# MEGAMOTHERBOARD.net
KiCad netlist of a schematic drawn in EAGLE
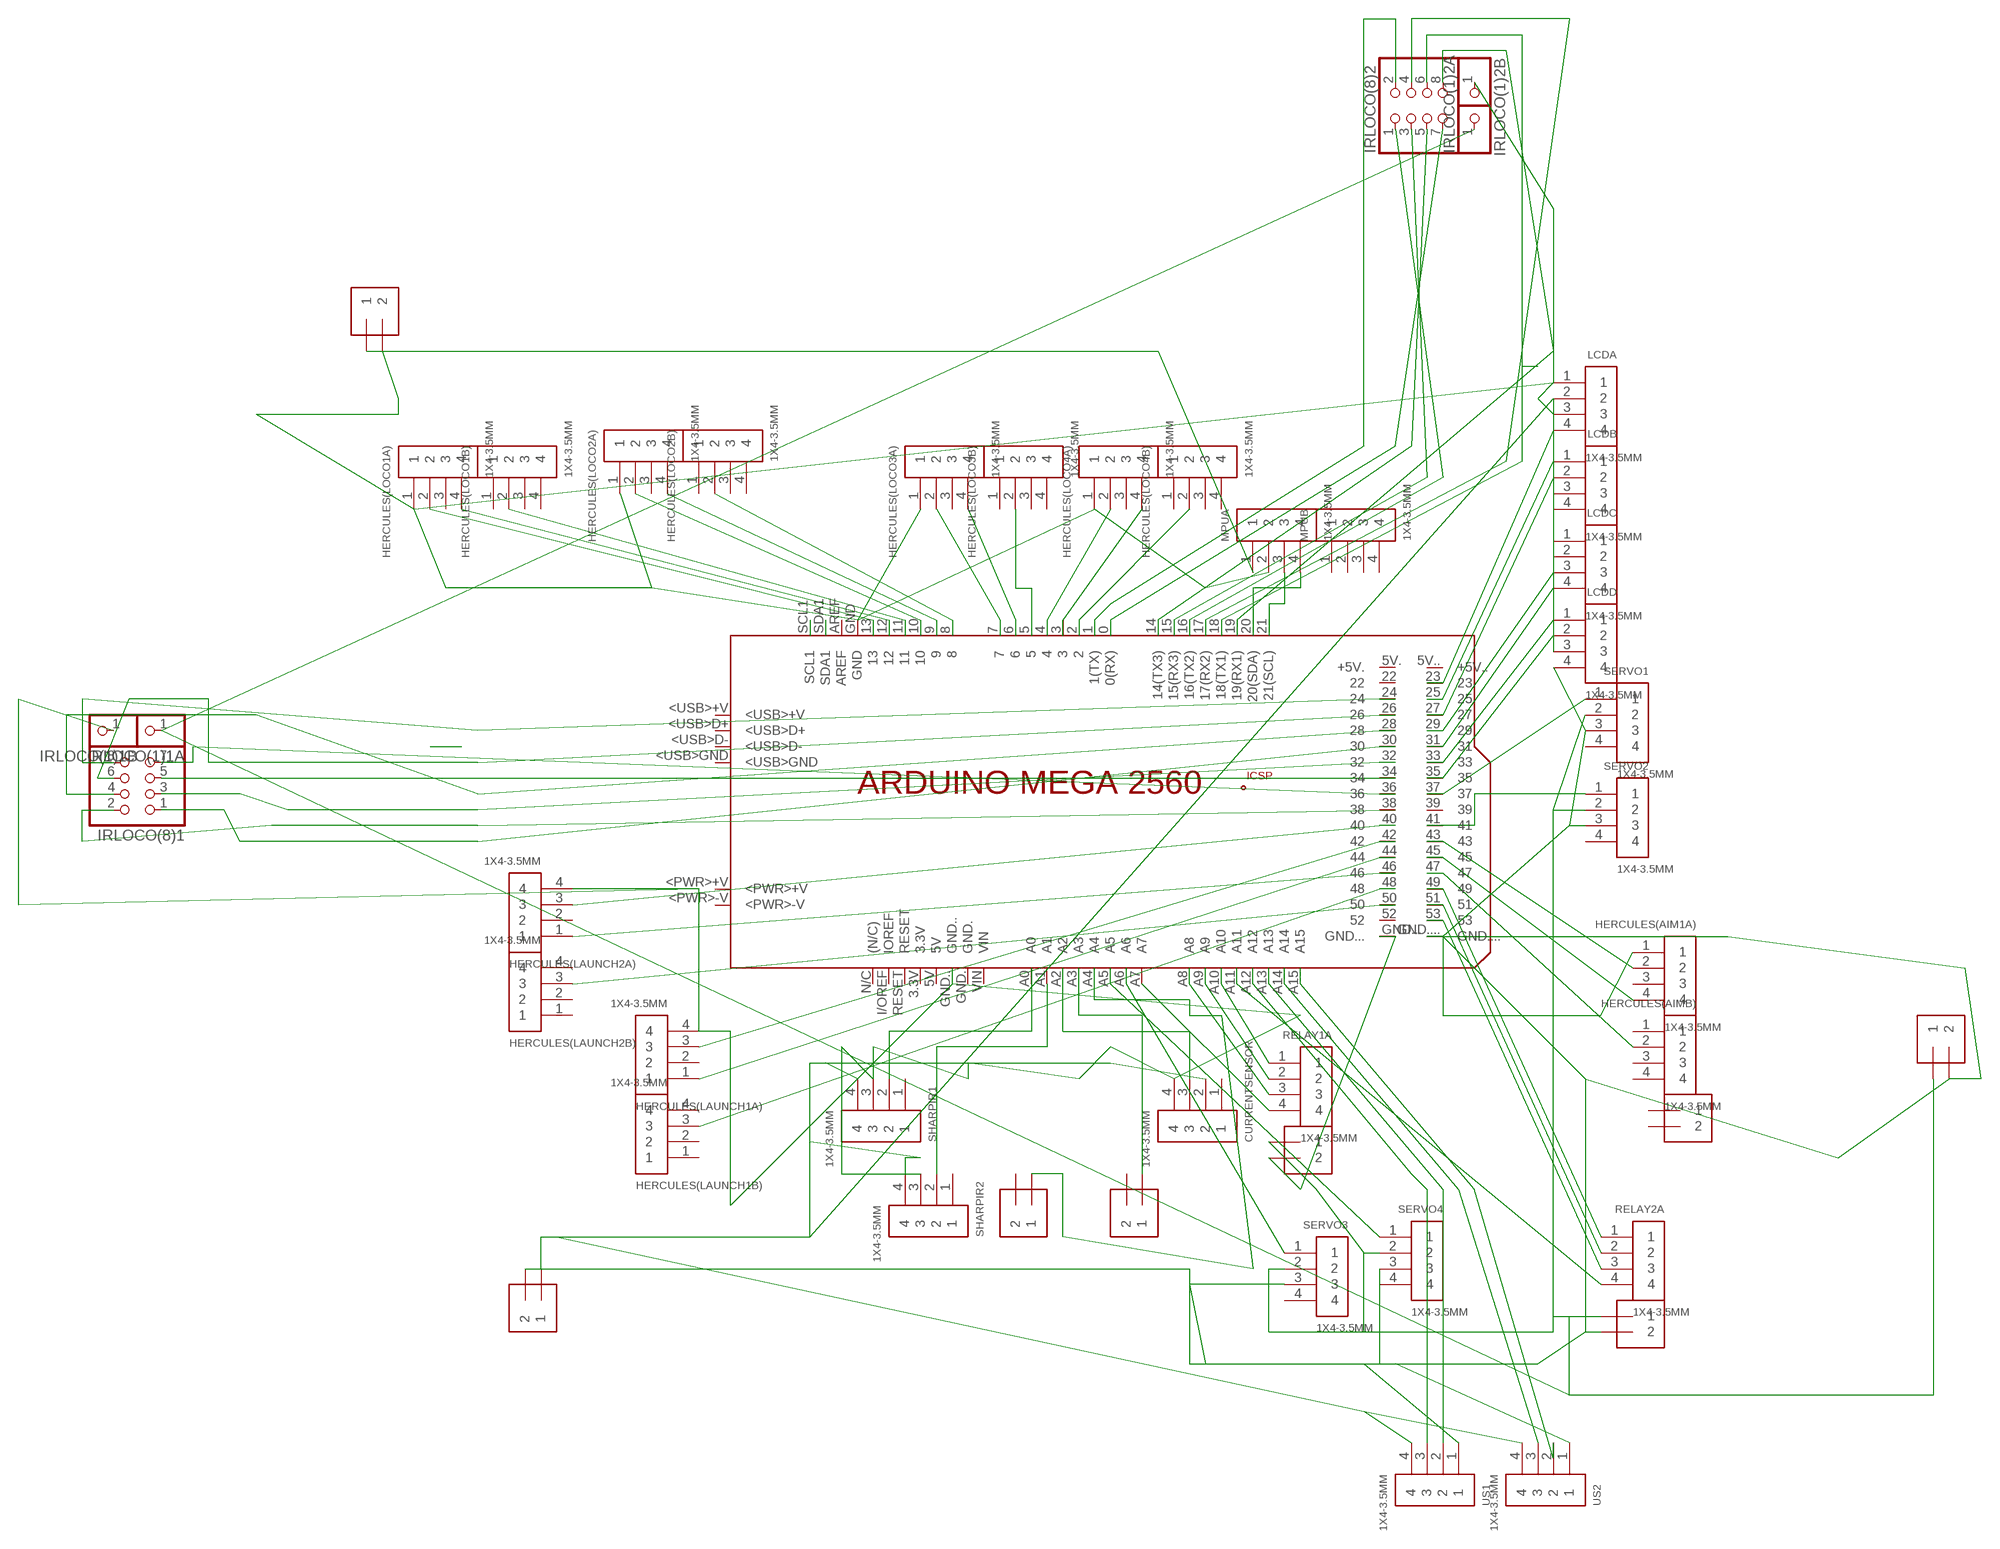
[diagram p0: schematic, sheet 1]

(export (version "E")
  (design (tool "Eeschema 10.0.6"))
  (components
    (comp (ref "3.3V")
      (value "1X2-3.5MM")
      (footprint "eagle-import:1X2-3.5MM")
      (libsource (lib "eagle-import") (part "1X2-3.5MM"))
    )
    (comp (ref "5V")
      (value "1X2-3.5MM")
      (footprint "eagle-import:1X2-3.5MM")
      (libsource (lib "eagle-import") (part "1X2-3.5MM"))
    )
    (comp (ref "12V")
      (value "1X2-3.5MM")
      (footprint "eagle-import:1X2-3.5MM")
      (libsource (lib "eagle-import") (part "1X2-3.5MM"))
    )
    (comp (ref "CURRENTSENSOR")
      (value "1X4-3.5MM")
      (footprint "eagle-import:1X04-3.5MM")
      (libsource (lib "eagle-import") (part "1X4-3.5MM"))
    )
    (comp (ref "HERCULES(AIM1A)")
      (value "1X4-3.5MM")
      (footprint "eagle-import:1X04-3.5MM")
      (libsource (lib "eagle-import") (part "1X4-3.5MM"))
    )
    (comp (ref "HERCULES(AIM1C)")
      (value "1X2-3.5MM")
      (footprint "eagle-import:1X2-3.5MM")
      (libsource (lib "eagle-import") (part "1X2-3.5MM"))
    )
    (comp (ref "HERCULES(AIMB)")
      (value "1X4-3.5MM")
      (footprint "eagle-import:1X04-3.5MM")
      (libsource (lib "eagle-import") (part "1X4-3.5MM"))
    )
    (comp (ref "HERCULES(LAUNCH1A)")
      (value "1X4-3.5MM")
      (footprint "eagle-import:1X04-3.5MM")
      (libsource (lib "eagle-import") (part "1X4-3.5MM"))
    )
    (comp (ref "HERCULES(LAUNCH1B)")
      (value "1X4-3.5MM")
      (footprint "eagle-import:1X04-3.5MM")
      (libsource (lib "eagle-import") (part "1X4-3.5MM"))
    )
    (comp (ref "HERCULES(LAUNCH2A)")
      (value "1X4-3.5MM")
      (footprint "eagle-import:1X04-3.5MM")
      (libsource (lib "eagle-import") (part "1X4-3.5MM"))
    )
    (comp (ref "HERCULES(LAUNCH2B)")
      (value "1X4-3.5MM")
      (footprint "eagle-import:1X04-3.5MM")
      (libsource (lib "eagle-import") (part "1X4-3.5MM"))
    )
    (comp (ref "HERCULES(LOCO1A)")
      (value "1X4-3.5MM")
      (footprint "eagle-import:1X04-3.5MM")
      (libsource (lib "eagle-import") (part "1X4-3.5MM"))
    )
    (comp (ref "HERCULES(LOCO1B)")
      (value "1X4-3.5MM")
      (footprint "eagle-import:1X04-3.5MM")
      (libsource (lib "eagle-import") (part "1X4-3.5MM"))
    )
    (comp (ref "HERCULES(LOCO2A)")
      (value "1X4-3.5MM")
      (footprint "eagle-import:1X04-3.5MM")
      (libsource (lib "eagle-import") (part "1X4-3.5MM"))
    )
    (comp (ref "HERCULES(LOCO2B)")
      (value "1X4-3.5MM")
      (footprint "eagle-import:1X04-3.5MM")
      (libsource (lib "eagle-import") (part "1X4-3.5MM"))
    )
    (comp (ref "HERCULES(LOCO3A)")
      (value "1X4-3.5MM")
      (footprint "eagle-import:1X04-3.5MM")
      (libsource (lib "eagle-import") (part "1X4-3.5MM"))
    )
    (comp (ref "HERCULES(LOCO3B)")
      (value "1X4-3.5MM")
      (footprint "eagle-import:1X04-3.5MM")
      (libsource (lib "eagle-import") (part "1X4-3.5MM"))
    )
    (comp (ref "HERCULES(LOCO4A)")
      (value "1X4-3.5MM")
      (footprint "eagle-import:1X04-3.5MM")
      (libsource (lib "eagle-import") (part "1X4-3.5MM"))
    )
    (comp (ref "HERCULES(LOCO4B)")
      (value "1X4-3.5MM")
      (footprint "eagle-import:1X04-3.5MM")
      (libsource (lib "eagle-import") (part "1X4-3.5MM"))
    )
    (comp (ref "IRLOCO(1)1A")
      (value "PINHD-1X1")
      (footprint "eagle-import:1X01")
      (libsource (lib "eagle-import") (part "PINHD-1X1"))
    )
    (comp (ref "IRLOCO(1)1B")
      (value "PINHD-1X1")
      (footprint "eagle-import:1X01")
      (libsource (lib "eagle-import") (part "PINHD-1X1"))
    )
    (comp (ref "IRLOCO(1)2A")
      (value "PINHD-1X1")
      (footprint "eagle-import:1X01")
      (libsource (lib "eagle-import") (part "PINHD-1X1"))
    )
    (comp (ref "IRLOCO(1)2B")
      (value "PINHD-1X1")
      (footprint "eagle-import:1X01")
      (libsource (lib "eagle-import") (part "PINHD-1X1"))
    )
    (comp (ref "IRLOCO(8)1")
      (value "PINHD-2X4")
      (footprint "eagle-import:2X04")
      (libsource (lib "eagle-import") (part "PINHD-2X4"))
    )
    (comp (ref "IRLOCO(8)2")
      (value "PINHD-2X4")
      (footprint "eagle-import:2X04")
      (libsource (lib "eagle-import") (part "PINHD-2X4"))
    )
    (comp (ref "IRLOCO1ANALOG")
      (value "1X2-3.5MM")
      (footprint "eagle-import:1X2-3.5MM")
      (libsource (lib "eagle-import") (part "1X2-3.5MM"))
    )
    (comp (ref "IRLOCO2ANALOG")
      (value "1X2-3.5MM")
      (footprint "eagle-import:1X2-3.5MM")
      (libsource (lib "eagle-import") (part "1X2-3.5MM"))
    )
    (comp (ref "LCDA")
      (value "1X4-3.5MM")
      (footprint "eagle-import:1X04-3.5MM")
      (libsource (lib "eagle-import") (part "1X4-3.5MM"))
    )
    (comp (ref "LCDB")
      (value "1X4-3.5MM")
      (footprint "eagle-import:1X04-3.5MM")
      (libsource (lib "eagle-import") (part "1X4-3.5MM"))
    )
    (comp (ref "LCDC")
      (value "1X4-3.5MM")
      (footprint "eagle-import:1X04-3.5MM")
      (libsource (lib "eagle-import") (part "1X4-3.5MM"))
    )
    (comp (ref "LCDD")
      (value "1X4-3.5MM")
      (footprint "eagle-import:1X04-3.5MM")
      (libsource (lib "eagle-import") (part "1X4-3.5MM"))
    )
    (comp (ref "MPUA")
      (value "1X4-3.5MM")
      (footprint "eagle-import:1X04-3.5MM")
      (libsource (lib "eagle-import") (part "1X4-3.5MM"))
    )
    (comp (ref "MPUB")
      (value "1X4-3.5MM")
      (footprint "eagle-import:1X04-3.5MM")
      (libsource (lib "eagle-import") (part "1X4-3.5MM"))
    )
    (comp (ref "PCB1")
      (value "ARDUINO_MEGA2560")
      (footprint "eagle-import:ARDUINO_MEGA2560")
      (libsource (lib "eagle-import") (part "ARDUINO_MEGA2560"))
    )
    (comp (ref "RELAY1A")
      (value "1X4-3.5MM")
      (footprint "eagle-import:1X04-3.5MM")
      (libsource (lib "eagle-import") (part "1X4-3.5MM"))
    )
    (comp (ref "RELAY1B")
      (value "1X2-3.5MM")
      (footprint "eagle-import:1X2-3.5MM")
      (libsource (lib "eagle-import") (part "1X2-3.5MM"))
    )
    (comp (ref "RELAY2A")
      (value "1X4-3.5MM")
      (footprint "eagle-import:1X04-3.5MM")
      (libsource (lib "eagle-import") (part "1X4-3.5MM"))
    )
    (comp (ref "RELAY2B")
      (value "1X2-3.5MM")
      (footprint "eagle-import:1X2-3.5MM")
      (libsource (lib "eagle-import") (part "1X2-3.5MM"))
    )
    (comp (ref "SERVO1")
      (value "1X4-3.5MM")
      (footprint "eagle-import:1X04-3.5MM")
      (libsource (lib "eagle-import") (part "1X4-3.5MM"))
    )
    (comp (ref "SERVO2")
      (value "1X4-3.5MM")
      (footprint "eagle-import:1X04-3.5MM")
      (libsource (lib "eagle-import") (part "1X4-3.5MM"))
    )
    (comp (ref "SERVO3")
      (value "1X4-3.5MM")
      (footprint "eagle-import:1X04-3.5MM")
      (libsource (lib "eagle-import") (part "1X4-3.5MM"))
    )
    (comp (ref "SERVO4")
      (value "1X4-3.5MM")
      (footprint "eagle-import:1X04-3.5MM")
      (libsource (lib "eagle-import") (part "1X4-3.5MM"))
    )
    (comp (ref "SHARPIR1")
      (value "1X4-3.5MM")
      (footprint "eagle-import:1X04-3.5MM")
      (libsource (lib "eagle-import") (part "1X4-3.5MM"))
    )
    (comp (ref "SHARPIR2")
      (value "1X4-3.5MM")
      (footprint "eagle-import:1X04-3.5MM")
      (libsource (lib "eagle-import") (part "1X4-3.5MM"))
    )
    (comp (ref "US1")
      (value "1X4-3.5MM")
      (footprint "eagle-import:1X04-3.5MM")
      (libsource (lib "eagle-import") (part "1X4-3.5MM"))
    )
    (comp (ref "US2")
      (value "1X4-3.5MM")
      (footprint "eagle-import:1X04-3.5MM")
      (libsource (lib "eagle-import") (part "1X4-3.5MM"))
    )
  )
  (nets
    (net (code "1") (name "Net-(3.3V-Pad1)") (class "Default")
      (node (ref "3.3V") (pin "1") (pinfunction "1_1") (pintype "passive"))
      (node (ref "MPUA") (pin "1") (pinfunction "1_1") (pintype "bidirectional"))
    )
    (net (code "2") (name "Net-(3.3V-Pad2)") (class "Default")
      (node (ref "3.3V") (pin "2") (pinfunction "2_2") (pintype "passive"))
      (node (ref "HERCULES(LOCO1A)") (pin "1") (pinfunction "1_1") (pintype "bidirectional"))
      (node (ref "HERCULES(LOCO2A)") (pin "1") (pinfunction "1_1") (pintype "bidirectional"))
      (node (ref "HERCULES(LOCO3A)") (pin "1") (pinfunction "1_1") (pintype "bidirectional"))
      (node (ref "HERCULES(LOCO4A)") (pin "1") (pinfunction "1_1") (pintype "bidirectional"))
      (node (ref "IRLOCO(1)2B") (pin "1") (pinfunction "1_1") (pintype "passive"))
      (node (ref "LCDA") (pin "1") (pinfunction "1_1") (pintype "bidirectional"))
      (node (ref "LCDA") (pin "3") (pinfunction "3_3") (pintype "bidirectional"))
      (node (ref "MPUA") (pin "2") (pinfunction "2_2") (pintype "bidirectional"))
      (node (ref "PCB1") (pin "GND") (pinfunction "GND_GND") (pintype "bidirectional"))
    )
    (net (code "3") (name "Net-(5V-Pad1)") (class "Default")
      (node (ref "5V") (pin "1") (pinfunction "1_1") (pintype "passive"))
      (node (ref "CURRENTSENSOR") (pin "2") (pinfunction "2_2") (pintype "bidirectional"))
      (node (ref "LCDA") (pin "2") (pinfunction "2_2") (pintype "bidirectional"))
      (node (ref "LCDD") (pin "3") (pinfunction "3_3") (pintype "bidirectional"))
      (node (ref "SHARPIR1") (pin "4") (pinfunction "4_4") (pintype "bidirectional"))
      (node (ref "SHARPIR2") (pin "4") (pinfunction "4_4") (pintype "bidirectional"))
      (node (ref "US1") (pin "4") (pinfunction "4_4") (pintype "bidirectional"))
      (node (ref "US2") (pin "4") (pinfunction "4_4") (pintype "bidirectional"))
    )
    (net (code "4") (name "Net-(12V-Pad1)") (class "Default")
      (node (ref "12V") (pin "1") (pinfunction "1_1") (pintype "passive"))
      (node (ref "IRLOCO(1)1A") (pin "1") (pinfunction "1_1") (pintype "passive"))
      (node (ref "IRLOCO(1)2A") (pin "1") (pinfunction "1_1") (pintype "passive"))
      (node (ref "RELAY1B") (pin "1") (pinfunction "1_1") (pintype "passive"))
      (node (ref "RELAY2B") (pin "1") (pinfunction "1_1") (pintype "passive"))
      (node (ref "SERVO1") (pin "2") (pinfunction "2_2") (pintype "bidirectional"))
      (node (ref "SERVO2") (pin "2") (pinfunction "2_2") (pintype "bidirectional"))
      (node (ref "SERVO3") (pin "2") (pinfunction "2_2") (pintype "bidirectional"))
      (node (ref "SERVO4") (pin "2") (pinfunction "2_2") (pintype "bidirectional"))
    )
    (net (code "5") (name "Net-(12V-Pad2)") (class "Default")
      (node (ref "12V") (pin "2") (pinfunction "2_2") (pintype "passive"))
      (node (ref "5V") (pin "2") (pinfunction "2_2") (pintype "passive"))
      (node (ref "HERCULES(AIM1A)") (pin "1") (pinfunction "1_1") (pintype "bidirectional"))
      (node (ref "LCDD") (pin "4") (pinfunction "4_4") (pintype "bidirectional"))
      (node (ref "PCB1") (pin "GND....") (pinfunction "GND...._GND....") (pintype "bidirectional"))
      (node (ref "RELAY2B") (pin "2") (pinfunction "2_2") (pintype "passive"))
      (node (ref "SERVO1") (pin "3") (pinfunction "3_3") (pintype "bidirectional"))
      (node (ref "SERVO2") (pin "3") (pinfunction "3_3") (pintype "bidirectional"))
      (node (ref "SERVO3") (pin "3") (pinfunction "3_3") (pintype "bidirectional"))
      (node (ref "SERVO4") (pin "3") (pinfunction "3_3") (pintype "bidirectional"))
      (node (ref "US1") (pin "1") (pinfunction "1_1") (pintype "bidirectional"))
      (node (ref "US2") (pin "1") (pinfunction "1_1") (pintype "bidirectional"))
    )
    (net (code "6") (name "Net-(CURRENTSENSOR-Pad3)") (class "Default")
      (node (ref "CURRENTSENSOR") (pin "3") (pinfunction "3_3") (pintype "bidirectional"))
      (node (ref "PCB1") (pin "A2") (pinfunction "A2_A2") (pintype "bidirectional"))
    )
    (net (code "7") (name "Net-(CURRENTSENSOR-Pad4)") (class "Default")
      (node (ref "CURRENTSENSOR") (pin "4") (pinfunction "4_4") (pintype "bidirectional"))
      (node (ref "HERCULES(LAUNCH1A)") (pin "4") (pinfunction "4_4") (pintype "bidirectional"))
      (node (ref "HERCULES(LAUNCH2A)") (pin "4") (pinfunction "4_4") (pintype "bidirectional"))
      (node (ref "IRLOCO(1)1B") (pin "1") (pinfunction "1_1") (pintype "passive"))
      (node (ref "PCB1") (pin "GND..") (pinfunction "GND.._GND..") (pintype "bidirectional"))
      (node (ref "SHARPIR1") (pin "3") (pinfunction "3_3") (pintype "bidirectional"))
      (node (ref "SHARPIR2") (pin "3") (pinfunction "3_3") (pintype "bidirectional"))
    )
    (net (code "8") (name "Net-(HERCULES(AIM1A)-Pad2)") (class "Default")
      (node (ref "HERCULES(AIM1A)") (pin "2") (pinfunction "2_2") (pintype "bidirectional"))
      (node (ref "PCB1") (pin "43") (pinfunction "43_43") (pintype "bidirectional"))
    )
    (net (code "9") (name "Net-(HERCULES(AIM1A)-Pad4)") (class "Default")
      (node (ref "HERCULES(AIM1A)") (pin "4") (pinfunction "4_4") (pintype "bidirectional"))
      (node (ref "PCB1") (pin "45") (pinfunction "45_45") (pintype "bidirectional"))
    )
    (net (code "10") (name "Net-(HERCULES(AIMB)-Pad2)") (class "Default")
      (node (ref "HERCULES(AIMB)") (pin "2") (pinfunction "2_2") (pintype "bidirectional"))
      (node (ref "PCB1") (pin "47") (pinfunction "47_47") (pintype "bidirectional"))
    )
    (net (code "11") (name "Net-(HERCULES(LAUNCH1A)-Pad1)") (class "Default")
      (node (ref "HERCULES(LAUNCH1A)") (pin "1") (pinfunction "1_1") (pintype "bidirectional"))
      (node (ref "PCB1") (pin "44") (pinfunction "44_44") (pintype "bidirectional"))
    )
    (net (code "12") (name "Net-(HERCULES(LAUNCH1A)-Pad3)") (class "Default")
      (node (ref "HERCULES(LAUNCH1A)") (pin "3") (pinfunction "3_3") (pintype "bidirectional"))
      (node (ref "PCB1") (pin "42") (pinfunction "42_42") (pintype "bidirectional"))
    )
    (net (code "13") (name "Net-(HERCULES(LAUNCH1B)-Pad3)") (class "Default")
      (node (ref "HERCULES(LAUNCH1B)") (pin "3") (pinfunction "3_3") (pintype "bidirectional"))
      (node (ref "PCB1") (pin "48") (pinfunction "48_48") (pintype "bidirectional"))
    )
    (net (code "14") (name "Net-(HERCULES(LAUNCH2A)-Pad1)") (class "Default")
      (node (ref "HERCULES(LAUNCH2A)") (pin "1") (pinfunction "1_1") (pintype "bidirectional"))
      (node (ref "PCB1") (pin "46") (pinfunction "46_46") (pintype "bidirectional"))
    )
    (net (code "15") (name "Net-(HERCULES(LAUNCH2A)-Pad3)") (class "Default")
      (node (ref "HERCULES(LAUNCH2A)") (pin "3") (pinfunction "3_3") (pintype "bidirectional"))
      (node (ref "PCB1") (pin "40") (pinfunction "40_40") (pintype "bidirectional"))
    )
    (net (code "16") (name "Net-(HERCULES(LAUNCH2B)-Pad3)") (class "Default")
      (node (ref "HERCULES(LAUNCH2B)") (pin "3") (pinfunction "3_3") (pintype "bidirectional"))
      (node (ref "PCB1") (pin "50") (pinfunction "50_50") (pintype "bidirectional"))
    )
    (net (code "17") (name "Net-(HERCULES(LOCO1A)-Pad2)") (class "Default")
      (node (ref "HERCULES(LOCO1A)") (pin "2") (pinfunction "2_2") (pintype "bidirectional"))
      (node (ref "PCB1") (pin "13") (pinfunction "13_13") (pintype "bidirectional"))
    )
    (net (code "18") (name "Net-(HERCULES(LOCO1A)-Pad4)") (class "Default")
      (node (ref "HERCULES(LOCO1A)") (pin "4") (pinfunction "4_4") (pintype "bidirectional"))
      (node (ref "PCB1") (pin "12") (pinfunction "12_12") (pintype "bidirectional"))
    )
    (net (code "19") (name "Net-(HERCULES(LOCO1B)-Pad2)") (class "Default")
      (node (ref "HERCULES(LOCO1B)") (pin "2") (pinfunction "2_2") (pintype "bidirectional"))
      (node (ref "PCB1") (pin "11") (pinfunction "11_11") (pintype "bidirectional"))
    )
    (net (code "20") (name "Net-(HERCULES(LOCO2A)-Pad2)") (class "Default")
      (node (ref "HERCULES(LOCO2A)") (pin "2") (pinfunction "2_2") (pintype "bidirectional"))
      (node (ref "PCB1") (pin "10") (pinfunction "10_10") (pintype "bidirectional"))
    )
    (net (code "21") (name "Net-(HERCULES(LOCO2A)-Pad4)") (class "Default")
      (node (ref "HERCULES(LOCO2A)") (pin "4") (pinfunction "4_4") (pintype "bidirectional"))
      (node (ref "PCB1") (pin "9") (pinfunction "9_9") (pintype "bidirectional"))
    )
    (net (code "22") (name "Net-(HERCULES(LOCO2B)-Pad2)") (class "Default")
      (node (ref "HERCULES(LOCO2B)") (pin "2") (pinfunction "2_2") (pintype "bidirectional"))
      (node (ref "PCB1") (pin "8") (pinfunction "8_8") (pintype "bidirectional"))
    )
    (net (code "23") (name "Net-(HERCULES(LOCO3A)-Pad2)") (class "Default")
      (node (ref "HERCULES(LOCO3A)") (pin "2") (pinfunction "2_2") (pintype "bidirectional"))
      (node (ref "PCB1") (pin "7") (pinfunction "7_7") (pintype "bidirectional"))
    )
    (net (code "24") (name "Net-(HERCULES(LOCO3A)-Pad4)") (class "Default")
      (node (ref "HERCULES(LOCO3A)") (pin "4") (pinfunction "4_4") (pintype "bidirectional"))
      (node (ref "PCB1") (pin "6") (pinfunction "6_6") (pintype "bidirectional"))
    )
    (net (code "25") (name "Net-(HERCULES(LOCO3B)-Pad2)") (class "Default")
      (node (ref "HERCULES(LOCO3B)") (pin "2") (pinfunction "2_2") (pintype "bidirectional"))
      (node (ref "PCB1") (pin "5") (pinfunction "5_5") (pintype "bidirectional"))
    )
    (net (code "26") (name "Net-(HERCULES(LOCO4A)-Pad2)") (class "Default")
      (node (ref "HERCULES(LOCO4A)") (pin "2") (pinfunction "2_2") (pintype "bidirectional"))
      (node (ref "PCB1") (pin "4") (pinfunction "4_4") (pintype "bidirectional"))
    )
    (net (code "27") (name "Net-(HERCULES(LOCO4A)-Pad4)") (class "Default")
      (node (ref "HERCULES(LOCO4A)") (pin "4") (pinfunction "4_4") (pintype "bidirectional"))
      (node (ref "PCB1") (pin "3") (pinfunction "3_3") (pintype "bidirectional"))
    )
    (net (code "28") (name "Net-(HERCULES(LOCO4B)-Pad2)") (class "Default")
      (node (ref "HERCULES(LOCO4B)") (pin "2") (pinfunction "2_2") (pintype "bidirectional"))
      (node (ref "PCB1") (pin "2") (pinfunction "2_2") (pintype "bidirectional"))
    )
    (net (code "29") (name "Net-(IRLOCO(8)1-Pad1)") (class "Default")
      (node (ref "IRLOCO(8)1") (pin "1") (pinfunction "1_1") (pintype "passive"))
      (node (ref "PCB1") (pin "30") (pinfunction "30_30") (pintype "bidirectional"))
    )
    (net (code "30") (name "Net-(IRLOCO(8)1-Pad2)") (class "Default")
      (node (ref "IRLOCO(8)1") (pin "2") (pinfunction "2_2") (pintype "passive"))
      (node (ref "PCB1") (pin "38") (pinfunction "38_38") (pintype "bidirectional"))
    )
    (net (code "31") (name "Net-(IRLOCO(8)1-Pad3)") (class "Default")
      (node (ref "IRLOCO(8)1") (pin "3") (pinfunction "3_3") (pintype "passive"))
      (node (ref "PCB1") (pin "32") (pinfunction "32_32") (pintype "bidirectional"))
    )
    (net (code "32") (name "Net-(IRLOCO(8)1-Pad4)") (class "Default")
      (node (ref "IRLOCO(8)1") (pin "4") (pinfunction "4_4") (pintype "passive"))
      (node (ref "PCB1") (pin "28") (pinfunction "28_28") (pintype "bidirectional"))
    )
    (net (code "33") (name "Net-(IRLOCO(8)1-Pad5)") (class "Default")
      (node (ref "IRLOCO(8)1") (pin "5") (pinfunction "5_5") (pintype "passive"))
      (node (ref "PCB1") (pin "34") (pinfunction "34_34") (pintype "bidirectional"))
    )
    (net (code "34") (name "Net-(IRLOCO(8)1-Pad6)") (class "Default")
      (node (ref "IRLOCO(8)1") (pin "6") (pinfunction "6_6") (pintype "passive"))
      (node (ref "PCB1") (pin "26") (pinfunction "26_26") (pintype "bidirectional"))
    )
    (net (code "35") (name "Net-(IRLOCO(8)1-Pad7)") (class "Default")
      (node (ref "IRLOCO(8)1") (pin "7") (pinfunction "7_7") (pintype "passive"))
      (node (ref "PCB1") (pin "36") (pinfunction "36_36") (pintype "bidirectional"))
    )
    (net (code "36") (name "Net-(IRLOCO(8)1-Pad8)") (class "Default")
      (node (ref "IRLOCO(8)1") (pin "8") (pinfunction "8_8") (pintype "passive"))
      (node (ref "PCB1") (pin "24") (pinfunction "24_24") (pintype "bidirectional"))
    )
    (net (code "37") (name "Net-(IRLOCO1ANALOG-Pad1)") (class "Default")
      (node (ref "IRLOCO1ANALOG") (pin "1") (pinfunction "1_1") (pintype "passive"))
      (node (ref "PCB1") (pin "A4") (pinfunction "A4_A4") (pintype "bidirectional"))
    )
    (net (code "38") (name "Net-(IRLOCO2ANALOG-Pad1)") (class "Default")
      (node (ref "IRLOCO2ANALOG") (pin "1") (pinfunction "1_1") (pintype "passive"))
      (node (ref "PCB1") (pin "A3") (pinfunction "A3_A3") (pintype "bidirectional"))
    )
    (net (code "39") (name "Net-(LCDA-Pad4)") (class "Default")
      (node (ref "LCDA") (pin "4") (pinfunction "4_4") (pintype "bidirectional"))
      (node (ref "PCB1") (pin "23") (pinfunction "23_23") (pintype "bidirectional"))
    )
    (net (code "40") (name "Net-(LCDB-Pad1)") (class "Default")
      (node (ref "LCDB") (pin "1") (pinfunction "1_1") (pintype "bidirectional"))
      (node (ref "PCB1") (pin "25") (pinfunction "25_25") (pintype "bidirectional"))
    )
    (net (code "41") (name "Net-(LCDB-Pad2)") (class "Default")
      (node (ref "LCDB") (pin "2") (pinfunction "2_2") (pintype "bidirectional"))
      (node (ref "PCB1") (pin "27") (pinfunction "27_27") (pintype "bidirectional"))
    )
    (net (code "42") (name "Net-(LCDC-Pad3)") (class "Default")
      (node (ref "LCDC") (pin "3") (pinfunction "3_3") (pintype "bidirectional"))
      (node (ref "PCB1") (pin "29") (pinfunction "29_29") (pintype "bidirectional"))
    )
    (net (code "43") (name "Net-(LCDC-Pad4)") (class "Default")
      (node (ref "LCDC") (pin "4") (pinfunction "4_4") (pintype "bidirectional"))
      (node (ref "PCB1") (pin "31") (pinfunction "31_31") (pintype "bidirectional"))
    )
    (net (code "44") (name "Net-(LCDD-Pad1)") (class "Default")
      (node (ref "LCDD") (pin "1") (pinfunction "1_1") (pintype "bidirectional"))
      (node (ref "PCB1") (pin "33") (pinfunction "33_33") (pintype "bidirectional"))
    )
    (net (code "45") (name "Net-(LCDD-Pad2)") (class "Default")
      (node (ref "LCDD") (pin "2") (pinfunction "2_2") (pintype "bidirectional"))
      (node (ref "PCB1") (pin "35") (pinfunction "35_35") (pintype "bidirectional"))
    )
    (net (code "46") (name "Net-(PCB1-0(RX))") (class "Default")
      (node (ref "IRLOCO(8)2") (pin "7") (pinfunction "7_7") (pintype "passive"))
      (node (ref "PCB1") (pin "0") (pinfunction "0(RX)_0") (pintype "bidirectional"))
    )
    (net (code "47") (name "Net-(PCB1-1(TX))") (class "Default")
      (node (ref "IRLOCO(8)2") (pin "2") (pinfunction "2_2") (pintype "passive"))
      (node (ref "PCB1") (pin "1") (pinfunction "1(TX)_1") (pintype "bidirectional"))
    )
    (net (code "48") (name "Net-(PCB1-14(TX3))") (class "Default")
      (node (ref "IRLOCO(8)2") (pin "5") (pinfunction "5_5") (pintype "passive"))
      (node (ref "PCB1") (pin "14") (pinfunction "14(TX3)_14") (pintype "bidirectional"))
    )
    (net (code "49") (name "Net-(PCB1-15(RX3))") (class "Default")
      (node (ref "IRLOCO(8)2") (pin "3") (pinfunction "3_3") (pintype "passive"))
      (node (ref "PCB1") (pin "15") (pinfunction "15(RX3)_15") (pintype "bidirectional"))
    )
    (net (code "50") (name "Net-(PCB1-16(TX2))") (class "Default")
      (node (ref "IRLOCO(8)2") (pin "1") (pinfunction "1_1") (pintype "passive"))
      (node (ref "PCB1") (pin "16") (pinfunction "16(TX2)_16") (pintype "bidirectional"))
    )
    (net (code "51") (name "Net-(PCB1-17(RX2))") (class "Default")
      (node (ref "IRLOCO(8)2") (pin "4") (pinfunction "4_4") (pintype "passive"))
      (node (ref "PCB1") (pin "17") (pinfunction "17(RX2)_17") (pintype "bidirectional"))
    )
    (net (code "52") (name "Net-(PCB1-18(TX1))") (class "Default")
      (node (ref "IRLOCO(8)2") (pin "6") (pinfunction "6_6") (pintype "passive"))
      (node (ref "PCB1") (pin "18") (pinfunction "18(TX1)_18") (pintype "bidirectional"))
    )
    (net (code "53") (name "Net-(PCB1-19(RX1))") (class "Default")
      (node (ref "IRLOCO(8)2") (pin "8") (pinfunction "8_8") (pintype "passive"))
      (node (ref "PCB1") (pin "19") (pinfunction "19(RX1)_19") (pintype "bidirectional"))
    )
    (net (code "54") (name "Net-(PCB1-20(SDA))") (class "Default")
      (node (ref "MPUA") (pin "4") (pinfunction "4_4") (pintype "bidirectional"))
      (node (ref "PCB1") (pin "20") (pinfunction "20(SDA)_20") (pintype "bidirectional"))
    )
    (net (code "55") (name "Net-(PCB1-21(SCL))") (class "Default")
      (node (ref "MPUA") (pin "3") (pinfunction "3_3") (pintype "bidirectional"))
      (node (ref "PCB1") (pin "21") (pinfunction "21(SCL)_21") (pintype "bidirectional"))
    )
    (net (code "56") (name "Net-(PCB1-Pad37)") (class "Default")
      (node (ref "PCB1") (pin "37") (pinfunction "37_37") (pintype "bidirectional"))
      (node (ref "SERVO1") (pin "1") (pinfunction "1_1") (pintype "bidirectional"))
    )
    (net (code "57") (name "Net-(PCB1-Pad41)") (class "Default")
      (node (ref "PCB1") (pin "41") (pinfunction "41_41") (pintype "bidirectional"))
      (node (ref "SERVO2") (pin "1") (pinfunction "1_1") (pintype "bidirectional"))
    )
    (net (code "58") (name "Net-(PCB1-Pad49)") (class "Default")
      (node (ref "PCB1") (pin "49") (pinfunction "49_49") (pintype "bidirectional"))
      (node (ref "RELAY2A") (pin "1") (pinfunction "1_1") (pintype "bidirectional"))
    )
    (net (code "59") (name "Net-(PCB1-Pad51)") (class "Default")
      (node (ref "PCB1") (pin "51") (pinfunction "51_51") (pintype "bidirectional"))
      (node (ref "RELAY2A") (pin "2") (pinfunction "2_2") (pintype "bidirectional"))
    )
    (net (code "60") (name "Net-(PCB1-Pad53)") (class "Default")
      (node (ref "PCB1") (pin "53") (pinfunction "53_53") (pintype "bidirectional"))
      (node (ref "RELAY2A") (pin "3") (pinfunction "3_3") (pintype "bidirectional"))
    )
    (net (code "61") (name "Net-(PCB1-PadA0)") (class "Default")
      (node (ref "PCB1") (pin "A0") (pinfunction "A0_A0") (pintype "bidirectional"))
      (node (ref "SHARPIR1") (pin "2") (pinfunction "2_2") (pintype "bidirectional"))
    )
    (net (code "62") (name "Net-(PCB1-PadA1)") (class "Default")
      (node (ref "PCB1") (pin "A1") (pinfunction "A1_A1") (pintype "bidirectional"))
      (node (ref "SHARPIR2") (pin "2") (pinfunction "2_2") (pintype "bidirectional"))
    )
    (net (code "63") (name "Net-(PCB1-PadA5)") (class "Default")
      (node (ref "PCB1") (pin "A5") (pinfunction "A5_A5") (pintype "bidirectional"))
      (node (ref "SERVO4") (pin "1") (pinfunction "1_1") (pintype "bidirectional"))
    )
    (net (code "64") (name "Net-(PCB1-PadA6)") (class "Default")
      (node (ref "PCB1") (pin "A6") (pinfunction "A6_A6") (pintype "bidirectional"))
      (node (ref "SERVO3") (pin "1") (pinfunction "1_1") (pintype "bidirectional"))
    )
    (net (code "65") (name "Net-(PCB1-PadA7)") (class "Default")
      (node (ref "PCB1") (pin "A7") (pinfunction "A7_A7") (pintype "bidirectional"))
      (node (ref "RELAY1A") (pin "4") (pinfunction "4_4") (pintype "bidirectional"))
    )
    (net (code "66") (name "Net-(PCB1-PadA8)") (class "Default")
      (node (ref "PCB1") (pin "A8") (pinfunction "A8_A8") (pintype "bidirectional"))
      (node (ref "RELAY1A") (pin "3") (pinfunction "3_3") (pintype "bidirectional"))
    )
    (net (code "67") (name "Net-(PCB1-PadA9)") (class "Default")
      (node (ref "PCB1") (pin "A9") (pinfunction "A9_A9") (pintype "bidirectional"))
      (node (ref "RELAY1A") (pin "2") (pinfunction "2_2") (pintype "bidirectional"))
    )
    (net (code "68") (name "Net-(PCB1-PadA10)") (class "Default")
      (node (ref "PCB1") (pin "A10") (pinfunction "A10_A10") (pintype "bidirectional"))
      (node (ref "RELAY1A") (pin "1") (pinfunction "1_1") (pintype "bidirectional"))
    )
    (net (code "69") (name "Net-(PCB1-PadA11)") (class "Default")
      (node (ref "PCB1") (pin "A11") (pinfunction "A11_A11") (pintype "bidirectional"))
      (node (ref "RELAY2A") (pin "4") (pinfunction "4_4") (pintype "bidirectional"))
    )
    (net (code "70") (name "Net-(PCB1-PadA12)") (class "Default")
      (node (ref "PCB1") (pin "A12") (pinfunction "A12_A12") (pintype "bidirectional"))
      (node (ref "US1") (pin "3") (pinfunction "3_3") (pintype "bidirectional"))
    )
    (net (code "71") (name "Net-(PCB1-PadA13)") (class "Default")
      (node (ref "PCB1") (pin "A13") (pinfunction "A13_A13") (pintype "bidirectional"))
      (node (ref "US1") (pin "2") (pinfunction "2_2") (pintype "bidirectional"))
    )
    (net (code "72") (name "Net-(PCB1-PadA14)") (class "Default")
      (node (ref "PCB1") (pin "A14") (pinfunction "A14_A14") (pintype "bidirectional"))
      (node (ref "US2") (pin "3") (pinfunction "3_3") (pintype "bidirectional"))
    )
    (net (code "73") (name "Net-(PCB1-PadA15)") (class "Default")
      (node (ref "PCB1") (pin "A15") (pinfunction "A15_A15") (pintype "bidirectional"))
      (node (ref "US2") (pin "2") (pinfunction "2_2") (pintype "bidirectional"))
    )
    (net (code "74") (name "Net-(PCB1-PadGND...)") (class "Default")
      (node (ref "PCB1") (pin "GND...") (pinfunction "GND..._GND...") (pintype "bidirectional"))
      (node (ref "RELAY1B") (pin "2") (pinfunction "2_2") (pintype "passive"))
    )
    (net (code "75") (name "unconnected-(CURRENTSENSOR-Pad1)") (class "Default")
      (node (ref "CURRENTSENSOR") (pin "1") (pinfunction "1_1") (pintype "bidirectional"))
    )
    (net (code "76") (name "unconnected-(HERCULES(AIM1A)-Pad3)") (class "Default")
      (node (ref "HERCULES(AIM1A)") (pin "3") (pinfunction "3_3") (pintype "bidirectional"))
    )
    (net (code "77") (name "unconnected-(HERCULES(AIM1C)-Pad1)") (class "Default")
      (node (ref "HERCULES(AIM1C)") (pin "1") (pinfunction "1_1") (pintype "passive"))
    )
    (net (code "78") (name "unconnected-(HERCULES(AIM1C)-Pad2)") (class "Default")
      (node (ref "HERCULES(AIM1C)") (pin "2") (pinfunction "2_2") (pintype "passive"))
    )
    (net (code "79") (name "unconnected-(HERCULES(AIMB)-Pad1)") (class "Default")
      (node (ref "HERCULES(AIMB)") (pin "1") (pinfunction "1_1") (pintype "bidirectional"))
    )
    (net (code "80") (name "unconnected-(HERCULES(AIMB)-Pad3)") (class "Default")
      (node (ref "HERCULES(AIMB)") (pin "3") (pinfunction "3_3") (pintype "bidirectional"))
    )
    (net (code "81") (name "unconnected-(HERCULES(AIMB)-Pad4)") (class "Default")
      (node (ref "HERCULES(AIMB)") (pin "4") (pinfunction "4_4") (pintype "bidirectional"))
    )
    (net (code "82") (name "unconnected-(HERCULES(LAUNCH1A)-Pad2)") (class "Default")
      (node (ref "HERCULES(LAUNCH1A)") (pin "2") (pinfunction "2_2") (pintype "bidirectional"))
    )
    (net (code "83") (name "unconnected-(HERCULES(LAUNCH1B)-Pad1)") (class "Default")
      (node (ref "HERCULES(LAUNCH1B)") (pin "1") (pinfunction "1_1") (pintype "bidirectional"))
    )
    (net (code "84") (name "unconnected-(HERCULES(LAUNCH1B)-Pad2)") (class "Default")
      (node (ref "HERCULES(LAUNCH1B)") (pin "2") (pinfunction "2_2") (pintype "bidirectional"))
    )
    (net (code "85") (name "unconnected-(HERCULES(LAUNCH1B)-Pad4)") (class "Default")
      (node (ref "HERCULES(LAUNCH1B)") (pin "4") (pinfunction "4_4") (pintype "bidirectional"))
    )
    (net (code "86") (name "unconnected-(HERCULES(LAUNCH2A)-Pad2)") (class "Default")
      (node (ref "HERCULES(LAUNCH2A)") (pin "2") (pinfunction "2_2") (pintype "bidirectional"))
    )
    (net (code "87") (name "unconnected-(HERCULES(LAUNCH2B)-Pad1)") (class "Default")
      (node (ref "HERCULES(LAUNCH2B)") (pin "1") (pinfunction "1_1") (pintype "bidirectional"))
    )
    (net (code "88") (name "unconnected-(HERCULES(LAUNCH2B)-Pad2)") (class "Default")
      (node (ref "HERCULES(LAUNCH2B)") (pin "2") (pinfunction "2_2") (pintype "bidirectional"))
    )
    (net (code "89") (name "unconnected-(HERCULES(LAUNCH2B)-Pad4)") (class "Default")
      (node (ref "HERCULES(LAUNCH2B)") (pin "4") (pinfunction "4_4") (pintype "bidirectional"))
    )
    (net (code "90") (name "unconnected-(HERCULES(LOCO1A)-Pad3)") (class "Default")
      (node (ref "HERCULES(LOCO1A)") (pin "3") (pinfunction "3_3") (pintype "bidirectional"))
    )
    (net (code "91") (name "unconnected-(HERCULES(LOCO1B)-Pad1)") (class "Default")
      (node (ref "HERCULES(LOCO1B)") (pin "1") (pinfunction "1_1") (pintype "bidirectional"))
    )
    (net (code "92") (name "unconnected-(HERCULES(LOCO1B)-Pad3)") (class "Default")
      (node (ref "HERCULES(LOCO1B)") (pin "3") (pinfunction "3_3") (pintype "bidirectional"))
    )
    (net (code "93") (name "unconnected-(HERCULES(LOCO1B)-Pad4)") (class "Default")
      (node (ref "HERCULES(LOCO1B)") (pin "4") (pinfunction "4_4") (pintype "bidirectional"))
    )
    (net (code "94") (name "unconnected-(HERCULES(LOCO2A)-Pad3)") (class "Default")
      (node (ref "HERCULES(LOCO2A)") (pin "3") (pinfunction "3_3") (pintype "bidirectional"))
    )
    (net (code "95") (name "unconnected-(HERCULES(LOCO2B)-Pad1)") (class "Default")
      (node (ref "HERCULES(LOCO2B)") (pin "1") (pinfunction "1_1") (pintype "bidirectional"))
    )
    (net (code "96") (name "unconnected-(HERCULES(LOCO2B)-Pad3)") (class "Default")
      (node (ref "HERCULES(LOCO2B)") (pin "3") (pinfunction "3_3") (pintype "bidirectional"))
    )
    (net (code "97") (name "unconnected-(HERCULES(LOCO2B)-Pad4)") (class "Default")
      (node (ref "HERCULES(LOCO2B)") (pin "4") (pinfunction "4_4") (pintype "bidirectional"))
    )
    (net (code "98") (name "unconnected-(HERCULES(LOCO3A)-Pad3)") (class "Default")
      (node (ref "HERCULES(LOCO3A)") (pin "3") (pinfunction "3_3") (pintype "bidirectional"))
    )
    (net (code "99") (name "unconnected-(HERCULES(LOCO3B)-Pad1)") (class "Default")
      (node (ref "HERCULES(LOCO3B)") (pin "1") (pinfunction "1_1") (pintype "bidirectional"))
    )
    (net (code "100") (name "unconnected-(HERCULES(LOCO3B)-Pad3)") (class "Default")
      (node (ref "HERCULES(LOCO3B)") (pin "3") (pinfunction "3_3") (pintype "bidirectional"))
    )
    (net (code "101") (name "unconnected-(HERCULES(LOCO3B)-Pad4)") (class "Default")
      (node (ref "HERCULES(LOCO3B)") (pin "4") (pinfunction "4_4") (pintype "bidirectional"))
    )
    (net (code "102") (name "unconnected-(HERCULES(LOCO4A)-Pad3)") (class "Default")
      (node (ref "HERCULES(LOCO4A)") (pin "3") (pinfunction "3_3") (pintype "bidirectional"))
    )
    (net (code "103") (name "unconnected-(HERCULES(LOCO4B)-Pad1)") (class "Default")
      (node (ref "HERCULES(LOCO4B)") (pin "1") (pinfunction "1_1") (pintype "bidirectional"))
    )
    (net (code "104") (name "unconnected-(HERCULES(LOCO4B)-Pad3)") (class "Default")
      (node (ref "HERCULES(LOCO4B)") (pin "3") (pinfunction "3_3") (pintype "bidirectional"))
    )
    (net (code "105") (name "unconnected-(HERCULES(LOCO4B)-Pad4)") (class "Default")
      (node (ref "HERCULES(LOCO4B)") (pin "4") (pinfunction "4_4") (pintype "bidirectional"))
    )
    (net (code "106") (name "unconnected-(IRLOCO1ANALOG-Pad2)") (class "Default")
      (node (ref "IRLOCO1ANALOG") (pin "2") (pinfunction "2_2") (pintype "passive"))
    )
    (net (code "107") (name "unconnected-(IRLOCO2ANALOG-Pad2)") (class "Default")
      (node (ref "IRLOCO2ANALOG") (pin "2") (pinfunction "2_2") (pintype "passive"))
    )
    (net (code "108") (name "unconnected-(LCDB-Pad3)") (class "Default")
      (node (ref "LCDB") (pin "3") (pinfunction "3_3") (pintype "bidirectional"))
    )
    (net (code "109") (name "unconnected-(LCDB-Pad4)") (class "Default")
      (node (ref "LCDB") (pin "4") (pinfunction "4_4") (pintype "bidirectional"))
    )
    (net (code "110") (name "unconnected-(LCDC-Pad1)") (class "Default")
      (node (ref "LCDC") (pin "1") (pinfunction "1_1") (pintype "bidirectional"))
    )
    (net (code "111") (name "unconnected-(LCDC-Pad2)") (class "Default")
      (node (ref "LCDC") (pin "2") (pinfunction "2_2") (pintype "bidirectional"))
    )
    (net (code "112") (name "unconnected-(MPUB-Pad1)") (class "Default")
      (node (ref "MPUB") (pin "1") (pinfunction "1_1") (pintype "bidirectional"))
    )
    (net (code "113") (name "unconnected-(MPUB-Pad2)") (class "Default")
      (node (ref "MPUB") (pin "2") (pinfunction "2_2") (pintype "bidirectional"))
    )
    (net (code "114") (name "unconnected-(MPUB-Pad3)") (class "Default")
      (node (ref "MPUB") (pin "3") (pinfunction "3_3") (pintype "bidirectional"))
    )
    (net (code "115") (name "unconnected-(MPUB-Pad4)") (class "Default")
      (node (ref "MPUB") (pin "4") (pinfunction "4_4") (pintype "bidirectional"))
    )
    (net (code "116") (name "unconnected-(PCB1-(N{slash}C)-PadN{slash}C)") (class "Default")
      (node (ref "PCB1") (pin "N/C") (pinfunction "(N/C)_N/C") (pintype "bidirectional"))
    )
    (net (code "117") (name "unconnected-(PCB1-+5V.-Pad5V.)") (class "Default")
      (node (ref "PCB1") (pin "5V.") (pinfunction "+5V._5V.") (pintype "bidirectional"))
    )
    (net (code "118") (name "unconnected-(PCB1-+5V..-Pad5V..)") (class "Default")
      (node (ref "PCB1") (pin "5V..") (pinfunction "+5V.._5V..") (pintype "bidirectional"))
    )
    (net (code "119") (name "unconnected-(PCB1-IOREF-PadI{slash}OREF)") (class "Default")
      (node (ref "PCB1") (pin "I/OREF") (pinfunction "IOREF_I/OREF") (pintype "bidirectional"))
    )
    (net (code "120") (name "unconnected-(PCB1-Pad+5V_)") (class "Default")
      (node (ref "PCB1") (pin "+5V_") (pinfunction "+5V__+5V_") (pintype "bidirectional"))
    )
    (net (code "121") (name "unconnected-(PCB1-Pad3.3V)") (class "Default")
      (node (ref "PCB1") (pin "3.3V") (pinfunction "3.3V_3.3V") (pintype "bidirectional"))
    )
    (net (code "122") (name "unconnected-(PCB1-Pad5V)") (class "Default")
      (node (ref "PCB1") (pin "5V") (pinfunction "5V_5V") (pintype "bidirectional"))
    )
    (net (code "123") (name "unconnected-(PCB1-Pad22)") (class "Default")
      (node (ref "PCB1") (pin "22") (pinfunction "22_22") (pintype "bidirectional"))
    )
    (net (code "124") (name "unconnected-(PCB1-Pad39)") (class "Default")
      (node (ref "PCB1") (pin "39") (pinfunction "39_39") (pintype "bidirectional"))
    )
    (net (code "125") (name "unconnected-(PCB1-Pad52)") (class "Default")
      (node (ref "PCB1") (pin "52") (pinfunction "52_52") (pintype "bidirectional"))
    )
    (net (code "126") (name "unconnected-(PCB1-Pad<PWR>+V)") (class "Default")
      (node (ref "PCB1") (pin "<PWR>+V") (pinfunction "<PWR>+V_<PWR>+V") (pintype "no_connect"))
    )
    (net (code "127") (name "unconnected-(PCB1-Pad<PWR>-V)") (class "Default")
      (node (ref "PCB1") (pin "<PWR>-V") (pinfunction "<PWR>-V_<PWR>-V") (pintype "no_connect"))
    )
    (net (code "128") (name "unconnected-(PCB1-Pad<USB>+V)") (class "Default")
      (node (ref "PCB1") (pin "<USB>+V") (pinfunction "<USB>+V_<USB>+V") (pintype "no_connect"))
    )
    (net (code "129") (name "unconnected-(PCB1-Pad<USB>D+)") (class "Default")
      (node (ref "PCB1") (pin "<USB>D+") (pinfunction "<USB>D+_<USB>D+") (pintype "no_connect"))
    )
    (net (code "130") (name "unconnected-(PCB1-Pad<USB>D-)") (class "Default")
      (node (ref "PCB1") (pin "<USB>D-") (pinfunction "<USB>D-_<USB>D-") (pintype "no_connect"))
    )
    (net (code "131") (name "unconnected-(PCB1-Pad<USB>GND)") (class "Default")
      (node (ref "PCB1") (pin "<USB>GND") (pinfunction "<USB>GND_<USB>GND") (pintype "no_connect"))
    )
    (net (code "132") (name "unconnected-(PCB1-PadAREF)") (class "Default")
      (node (ref "PCB1") (pin "AREF") (pinfunction "AREF_AREF") (pintype "bidirectional"))
    )
    (net (code "133") (name "unconnected-(PCB1-PadGND.)") (class "Default")
      (node (ref "PCB1") (pin "GND.") (pinfunction "GND._GND.") (pintype "bidirectional"))
    )
    (net (code "134") (name "unconnected-(PCB1-PadGND__)") (class "Default")
      (node (ref "PCB1") (pin "GND__") (pinfunction "GND___GND__") (pintype "bidirectional"))
    )
    (net (code "135") (name "unconnected-(PCB1-PadMISO)") (class "Default")
      (node (ref "PCB1") (pin "MISO") (pinfunction "MISO_MISO") (pintype "bidirectional"))
    )
    (net (code "136") (name "unconnected-(PCB1-PadMOSI)") (class "Default")
      (node (ref "PCB1") (pin "MOSI") (pinfunction "MOSI_MOSI") (pintype "bidirectional"))
    )
    (net (code "137") (name "unconnected-(PCB1-PadRESET)") (class "Default")
      (node (ref "PCB1") (pin "RESET") (pinfunction "RESET_RESET") (pintype "bidirectional"))
    )
    (net (code "138") (name "unconnected-(PCB1-PadRESET.)") (class "Default")
      (node (ref "PCB1") (pin "RESET.") (pinfunction "RESET._RESET.") (pintype "bidirectional"))
    )
    (net (code "139") (name "unconnected-(PCB1-PadSCK)") (class "Default")
      (node (ref "PCB1") (pin "SCK") (pinfunction "SCK_SCK") (pintype "bidirectional"))
    )
    (net (code "140") (name "unconnected-(PCB1-PadSCL1)") (class "Default")
      (node (ref "PCB1") (pin "SCL1") (pinfunction "SCL1_SCL1") (pintype "bidirectional"))
    )
    (net (code "141") (name "unconnected-(PCB1-PadSDA1)") (class "Default")
      (node (ref "PCB1") (pin "SDA1") (pinfunction "SDA1_SDA1") (pintype "bidirectional"))
    )
    (net (code "142") (name "unconnected-(PCB1-PadVIN)") (class "Default")
      (node (ref "PCB1") (pin "VIN") (pinfunction "VIN_VIN") (pintype "bidirectional"))
    )
    (net (code "143") (name "unconnected-(SERVO1-Pad4)") (class "Default")
      (node (ref "SERVO1") (pin "4") (pinfunction "4_4") (pintype "bidirectional"))
    )
    (net (code "144") (name "unconnected-(SERVO2-Pad4)") (class "Default")
      (node (ref "SERVO2") (pin "4") (pinfunction "4_4") (pintype "bidirectional"))
    )
    (net (code "145") (name "unconnected-(SERVO3-Pad4)") (class "Default")
      (node (ref "SERVO3") (pin "4") (pinfunction "4_4") (pintype "bidirectional"))
    )
    (net (code "146") (name "unconnected-(SERVO4-Pad4)") (class "Default")
      (node (ref "SERVO4") (pin "4") (pinfunction "4_4") (pintype "bidirectional"))
    )
    (net (code "147") (name "unconnected-(SHARPIR1-Pad1)") (class "Default")
      (node (ref "SHARPIR1") (pin "1") (pinfunction "1_1") (pintype "bidirectional"))
    )
    (net (code "148") (name "unconnected-(SHARPIR2-Pad1)") (class "Default")
      (node (ref "SHARPIR2") (pin "1") (pinfunction "1_1") (pintype "bidirectional"))
    )
  )
)
